# PSU.net
KiCad netlist of a schematic drawn in Altium Designer
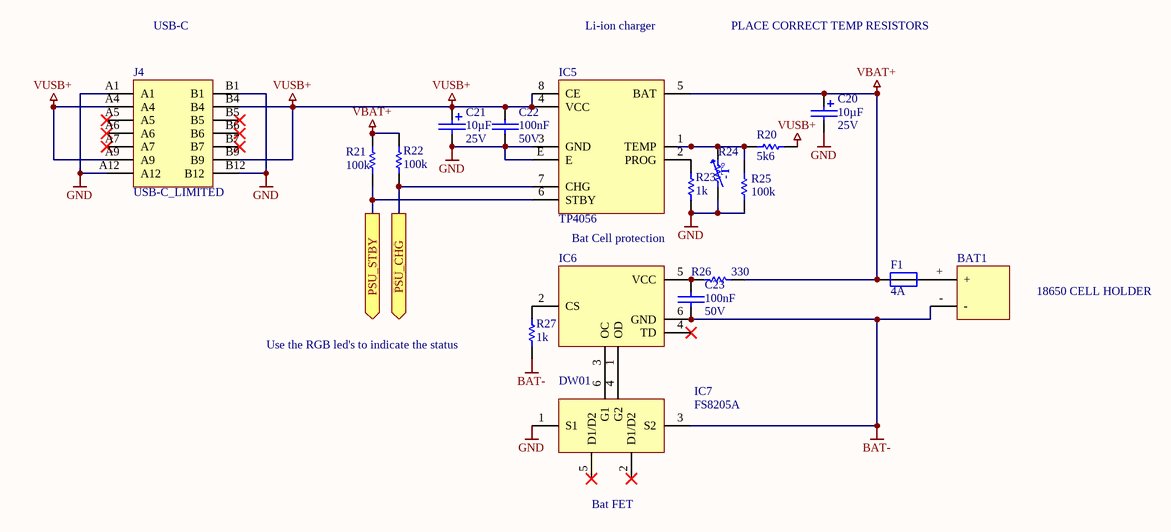
[diagram p0: PSU.SchDoc]

(export (version "E")
  (design (tool "Eeschema 10.0.6"))
  (components
    (comp (ref "BAT1")
      (value "18650 CELL HOLDER")
      (footprint "T353")
      (description "18650 single cell Battery holder")
      (fields (field (name "MANUFACTURER") "GTIWUNG"))
      (libsource (lib "js-altium-library") (part "2AA_BAT_HOLDER"))
    )
    (comp (ref "C20")
      (value "10µF")
      (footprint "CD6.3H12TH")
      (description "CAP ALUM 10UF 20% 25V TH")
      (fields
        (field (name "MANUFACTURER") "Yunxing")
        (field (name "TOLERANCE") "20%")
        (field (name "VOLTAGE") "25V")
      )
      (libsource (lib "js-altium-library") (part "cap-pol"))
    )
    (comp (ref "C21")
      (value "10µF")
      (footprint "CD6.3H12TH")
      (description "CAP ALUM 10UF 20% 25V TH")
      (fields
        (field (name "MANUFACTURER") "Yunxing")
        (field (name "TOLERANCE") "20%")
        (field (name "VOLTAGE") "25V")
      )
      (libsource (lib "js-altium-library") (part "cap-pol"))
    )
    (comp (ref "C22")
      (value "100nF")
      (footprint "TH5.08")
      (description "CAP CER TH 100nF X7R 50V")
      (fields
        (field (name "MANUFACTURER") "FH")
        (field (name "TOLERANCE") "10%")
        (field (name "VOLTAGE") "50V")
      )
      (libsource (lib "js-altium-library") (part "cap_non_pol"))
    )
    (comp (ref "C23")
      (value "100nF")
      (footprint "TH5.08")
      (description "CAP CER TH 100nF X7R 50V")
      (fields
        (field (name "MANUFACTURER") "FH")
        (field (name "TOLERANCE") "10%")
        (field (name "VOLTAGE") "50V")
      )
      (libsource (lib "js-altium-library") (part "cap_non_pol"))
    )
    (comp (ref "F1")
      (value "4A")
      (footprint "F0603")
      (description "FUSE BOARD MOUNT 4A 32VDC 0603")
      (fields
        (field (name "MANUFACTURER") "Vishay Beyschlag/Draloric/BC Components")
        (field (name "Comment") "fuse")
      )
      (libsource (lib "js-altium-library") (part "fuse"))
    )
    (comp (ref "IC5") (value "TP4056") (libsource (lib "ic") (part "TP4056")))
    (comp (ref "IC6")
      (value "DW01")
      (footprint "SOT-23-6")
      (description "IC  Battery Management IC")
      (fields (field (name "MANUFACTURER") "Fortune Semicon"))
      (libsource (lib "js-altium-library") (part "DW01"))
    )
    (comp (ref "IC7")
      (value "FS8205A")
      (footprint "SOT-23-6")
      (description "IC  MOSFET Array 3A")
      (fields (field (name "MANUFACTURER") "TECH PUBLIC"))
      (libsource (lib "js-altium-library") (part "FS8205A"))
    )
    (comp (ref "J4")
      (value "USB-C_LIMITED")
      (footprint "GT-USB-7037")
      (description "USB TYPE C , RECEPTACLE, R/A")
      (fields (field (name "MANUFACTURER") "G-Switch"))
      (libsource (lib "js-altium-library") (part "USB-C_LIMITED"))
    )
    (comp (ref "R20")
      (value "5k6")
      (footprint "TH6.3")
      (description "RES TH 4k12 OHM 1% 1/4W")
      (fields (field (name "MANUFACTURER") "UNI-ROYAL(Uniroyal Elec)") (field (name "TOLERANCE") "0,01"))
      (libsource (lib "js-altium-library") (part "resistor"))
    )
    (comp (ref "R21")
      (value "100k")
      (footprint "TH6.3")
      (description "RES TH 100k OHM 5% 1/4W")
      (fields (field (name "MANUFACTURER") "VO") (field (name "TOLERANCE") "5%"))
      (libsource (lib "js-altium-library") (part "resistor"))
    )
    (comp (ref "R22")
      (value "100k")
      (footprint "TH6.3")
      (description "RES TH 100k OHM 5% 1/4W")
      (fields (field (name "MANUFACTURER") "VO") (field (name "TOLERANCE") "5%"))
      (libsource (lib "js-altium-library") (part "resistor"))
    )
    (comp (ref "R23")
      (value "1k")
      (footprint "TH6.3")
      (description "RES TH 1k OHM 5% 1/4W")
      (fields (field (name "MANUFACTURER") "VO") (field (name "TOLERANCE") "5%"))
      (libsource (lib "js-altium-library") (part "resistor"))
    )
    (comp (ref "R24")
      (value "thermistor")
      (footprint "TH6.3")
      (description "THERMISTOR NTC 10KOHM 3435K BEAD")
      (fields (field (name "MANUFACTURER") "Nanjing Shiheng Elec") (field (name "TOLERANCE") "5%"))
      (libsource (lib "js-altium-library") (part "thermistor"))
    )
    (comp (ref "R25")
      (value "100k")
      (footprint "TH6.3")
      (description "RES TH 100k OHM 5% 1/4W")
      (fields (field (name "MANUFACTURER") "VO") (field (name "TOLERANCE") "5%"))
      (libsource (lib "js-altium-library") (part "resistor"))
    )
    (comp (ref "R26")
      (value "330")
      (footprint "TH6.3")
      (description "RES TH 330 OHM 5% 1/4W")
      (fields (field (name "MANUFACTURER") "VO") (field (name "TOLERANCE") "5%"))
      (libsource (lib "js-altium-library") (part "resistor"))
    )
    (comp (ref "R27")
      (value "1k")
      (footprint "TH6.3")
      (description "RES TH 1k OHM 5% 1/4W")
      (fields (field (name "MANUFACTURER") "VO") (field (name "TOLERANCE") "5%"))
      (libsource (lib "js-altium-library") (part "resistor"))
    )
  )
  (nets
    (net (code "1") (name "/PSU_CHG") (class "Default")
      (node (ref "IC5") (pin "7") (pinfunction "CHG_7") (pintype "passive"))
      (node (ref "R22") (pin "2") (pinfunction "2_2") (pintype "passive"))
    )
    (net (code "2") (name "/PSU_STBY") (class "Default")
      (node (ref "IC5") (pin "6") (pinfunction "STBY_6") (pintype "passive"))
      (node (ref "R21") (pin "1") (pinfunction "1_1") (pintype "passive"))
    )
    (net (code "3") (name "BAT-") (class "Default")
      (node (ref "BAT1") (pin "-") (pinfunction "-_-") (pintype "passive"))
      (node (ref "C23") (pin "2") (pinfunction "2_2") (pintype "passive"))
      (node (ref "IC6") (pin "6") (pinfunction "GND_6") (pintype "passive"))
      (node (ref "IC7") (pin "3") (pinfunction "S2_3") (pintype "passive"))
      (node (ref "R27") (pin "2") (pinfunction "2_2") (pintype "passive"))
    )
    (net (code "4") (name "GND") (class "Default")
      (node (ref "C20") (pin "-") (pinfunction "-_-") (pintype "passive"))
      (node (ref "C21") (pin "-") (pinfunction "-_-") (pintype "passive"))
      (node (ref "C22") (pin "2") (pinfunction "2_2") (pintype "passive"))
      (node (ref "IC5") (pin "3") (pinfunction "GND_3") (pintype "passive"))
      (node (ref "IC5") (pin "E") (pinfunction "E_E") (pintype "passive"))
      (node (ref "IC7") (pin "1") (pinfunction "S1_1") (pintype "passive"))
      (node (ref "J4") (pin "A1") (pinfunction "A1_A1") (pintype "passive"))
      (node (ref "J4") (pin "A12") (pinfunction "A12_A12") (pintype "passive"))
      (node (ref "J4") (pin "B1") (pinfunction "B1_B1") (pintype "passive"))
      (node (ref "J4") (pin "B12") (pinfunction "B12_B12") (pintype "passive"))
      (node (ref "R23") (pin "2") (pinfunction "2_2") (pintype "passive"))
      (node (ref "R24") (pin "1") (pinfunction "1_1") (pintype "passive"))
      (node (ref "R25") (pin "1") (pinfunction "1_1") (pintype "passive"))
    )
    (net (code "5") (name "Net-(BAT1-Pad+)") (class "Default")
      (node (ref "BAT1") (pin "+") (pinfunction "+_+") (pintype "passive"))
      (node (ref "F1") (pin "2") (pinfunction "2_2") (pintype "passive"))
    )
    (net (code "6") (name "Net-(IC5-PROG)") (class "Default")
      (node (ref "IC5") (pin "2") (pinfunction "PROG_2") (pintype "passive"))
      (node (ref "R23") (pin "1") (pinfunction "1_1") (pintype "passive"))
    )
    (net (code "7") (name "Net-(IC5-TEMP)") (class "Default")
      (node (ref "IC5") (pin "1") (pinfunction "TEMP_1") (pintype "passive"))
      (node (ref "R20") (pin "1") (pinfunction "1_1") (pintype "passive"))
      (node (ref "R24") (pin "2") (pinfunction "2_2") (pintype "passive"))
      (node (ref "R25") (pin "2") (pinfunction "2_2") (pintype "passive"))
    )
    (net (code "8") (name "Net-(IC6-CS)") (class "Default")
      (node (ref "IC6") (pin "2") (pinfunction "CS_2") (pintype "passive"))
      (node (ref "R27") (pin "1") (pinfunction "1_1") (pintype "passive"))
    )
    (net (code "9") (name "Net-(IC6-OC)") (class "Default")
      (node (ref "IC6") (pin "3") (pinfunction "OC_3") (pintype "passive"))
      (node (ref "IC7") (pin "6") (pinfunction "G1_6") (pintype "passive"))
    )
    (net (code "10") (name "Net-(IC6-OD)") (class "Default")
      (node (ref "IC6") (pin "1") (pinfunction "OD_1") (pintype "passive"))
      (node (ref "IC7") (pin "4") (pinfunction "G2_4") (pintype "passive"))
    )
    (net (code "11") (name "Net-(IC6-VCC)") (class "Default")
      (node (ref "C23") (pin "1") (pinfunction "1_1") (pintype "passive"))
      (node (ref "IC6") (pin "5") (pinfunction "VCC_5") (pintype "passive"))
      (node (ref "R26") (pin "1") (pinfunction "1_1") (pintype "passive"))
    )
    (net (code "12") (name "VBAT+") (class "Default")
      (node (ref "C20") (pin "+") (pinfunction "+_+") (pintype "passive"))
      (node (ref "F1") (pin "1") (pinfunction "1_1") (pintype "passive"))
      (node (ref "IC5") (pin "5") (pinfunction "BAT_5") (pintype "passive"))
      (node (ref "R21") (pin "2") (pinfunction "2_2") (pintype "passive"))
      (node (ref "R22") (pin "1") (pinfunction "1_1") (pintype "passive"))
      (node (ref "R26") (pin "2") (pinfunction "2_2") (pintype "passive"))
    )
    (net (code "13") (name "VUSB+") (class "Default")
      (node (ref "C21") (pin "+") (pinfunction "+_+") (pintype "passive"))
      (node (ref "C22") (pin "1") (pinfunction "1_1") (pintype "passive"))
      (node (ref "IC5") (pin "4") (pinfunction "VCC_4") (pintype "passive"))
      (node (ref "IC5") (pin "8") (pinfunction "CE_8") (pintype "passive"))
      (node (ref "J4") (pin "A4") (pinfunction "A4_A4") (pintype "passive"))
      (node (ref "J4") (pin "A9") (pinfunction "A9_A9") (pintype "passive"))
      (node (ref "J4") (pin "B4") (pinfunction "B4_B4") (pintype "passive"))
      (node (ref "J4") (pin "B9") (pinfunction "B9_B9") (pintype "passive"))
      (node (ref "R20") (pin "2") (pinfunction "2_2") (pintype "passive"))
    )
    (net (code "14") (name "unconnected-(IC6-TD-Pad4)") (class "Default")
      (node (ref "IC6") (pin "4") (pinfunction "TD_4") (pintype "passive+no_connect"))
    )
    (net (code "15") (name "unconnected-(IC7-D1{slash}D2-Pad2)") (class "Default")
      (node (ref "IC7") (pin "2") (pinfunction "D1/D2_2") (pintype "passive+no_connect"))
    )
    (net (code "16") (name "unconnected-(IC7-D1{slash}D2-Pad5)") (class "Default")
      (node (ref "IC7") (pin "5") (pinfunction "D1/D2_5") (pintype "passive+no_connect"))
    )
    (net (code "17") (name "unconnected-(J4-PadA5)") (class "Default")
      (node (ref "J4") (pin "A5") (pinfunction "A5_A5") (pintype "passive+no_connect"))
    )
    (net (code "18") (name "unconnected-(J4-PadA6)") (class "Default")
      (node (ref "J4") (pin "A6") (pinfunction "A6_A6") (pintype "passive+no_connect"))
    )
    (net (code "19") (name "unconnected-(J4-PadA7)") (class "Default")
      (node (ref "J4") (pin "A7") (pinfunction "A7_A7") (pintype "passive+no_connect"))
    )
    (net (code "20") (name "unconnected-(J4-PadB5)") (class "Default")
      (node (ref "J4") (pin "B5") (pinfunction "B5_B5") (pintype "passive+no_connect"))
    )
    (net (code "21") (name "unconnected-(J4-PadB6)") (class "Default")
      (node (ref "J4") (pin "B6") (pinfunction "B6_B6") (pintype "passive+no_connect"))
    )
    (net (code "22") (name "unconnected-(J4-PadB7)") (class "Default")
      (node (ref "J4") (pin "B7") (pinfunction "B7_B7") (pintype "passive+no_connect"))
    )
  )
)
